# Audio_Jack_Interface.net
KiCad netlist of a schematic drawn in EAGLE
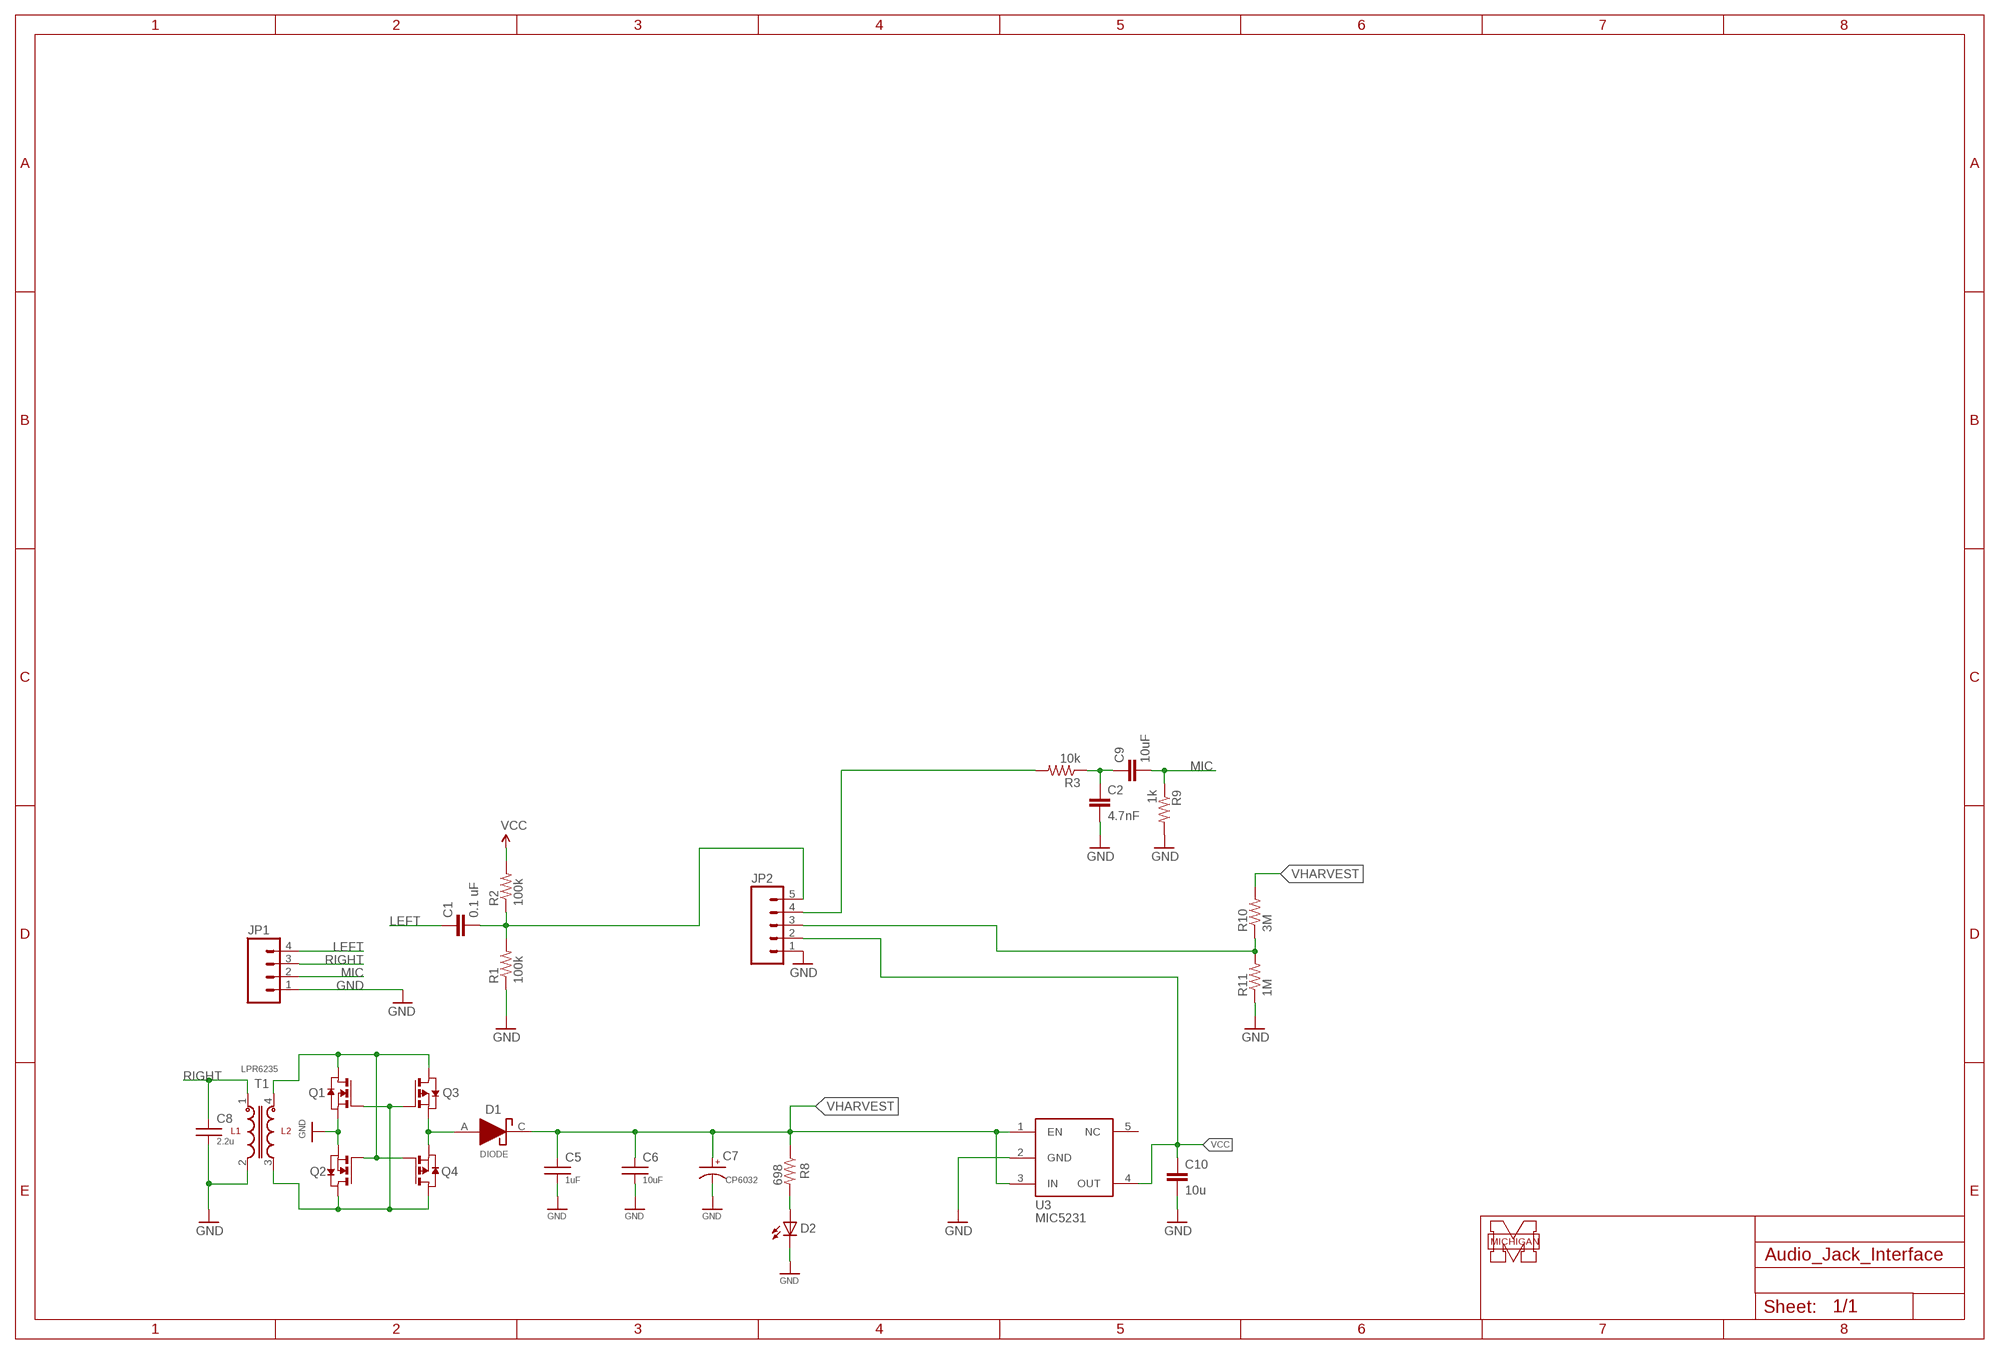
[diagram p0: schematic, sheet 1]

(export (version "E")
  (design (tool "Eeschema 10.0.6"))
  (components
    (comp (ref "C1")
      (value "0.1 uF")
      (footprint "eagle-import:0603-CAP")
      (libsource (lib "eagle-import") (part "CAP0603-CAP"))
    )
    (comp (ref "C2")
      (value "4.7nF")
      (footprint "eagle-import:0603-CAP")
      (libsource (lib "eagle-import") (part "CAP0603-CAP"))
    )
    (comp (ref "C5")
      (value "1uF")
      (footprint "eagle-import:C0603")
      (libsource (lib "eagle-import") (part "C0603"))
    )
    (comp (ref "C6")
      (value "10uF")
      (footprint "eagle-import:C0603")
      (libsource (lib "eagle-import") (part "C0603"))
    )
    (comp (ref "C7")
      (value "CP6032")
      (footprint "eagle-import:CT6032")
      (libsource (lib "eagle-import") (part "CP6032"))
    )
    (comp (ref "C8")
      (value "2.2u")
      (footprint "eagle-import:C0603")
      (libsource (lib "eagle-import") (part "C0603"))
    )
    (comp (ref "C9")
      (value "10uF")
      (footprint "eagle-import:0603-CAP")
      (libsource (lib "eagle-import") (part "CAP0603-CAP"))
    )
    (comp (ref "C10")
      (value "10u")
      (footprint "eagle-import:C0603")
      (libsource (lib "eagle-import") (part "C-EUC0603"))
    )
    (comp (ref "D1")
      (value "DIODE")
      (footprint "eagle-import:MINIMELF")
      (libsource (lib "eagle-import") (part "DIODE"))
    )
    (comp (ref "D2")
      (value "LED0603")
      (footprint "eagle-import:LED-0603")
      (libsource (lib "eagle-import") (part "LED0603"))
    )
    (comp (ref "JP1")
      (value "M041.27MM")
      (footprint "eagle-import:1X04-1.27MM")
      (libsource (lib "eagle-import") (part "M041.27MM"))
    )
    (comp (ref "JP2")
      (value "M05PTH")
      (footprint "eagle-import:1X05")
      (libsource (lib "eagle-import") (part "M05PTH"))
    )
    (comp (ref "Q1")
      (value "NMOSSOT23")
      (footprint "eagle-import:SOT-23")
      (libsource (lib "eagle-import") (part "NMOSSOT23"))
    )
    (comp (ref "Q2")
      (value "NMOSSOT23")
      (footprint "eagle-import:SOT-23")
      (libsource (lib "eagle-import") (part "NMOSSOT23"))
    )
    (comp (ref "Q3")
      (value "PMOSSOT23")
      (footprint "eagle-import:SOT-23")
      (libsource (lib "eagle-import") (part "PMOSSOT23"))
    )
    (comp (ref "Q4")
      (value "PMOSSOT23")
      (footprint "eagle-import:SOT-23")
      (libsource (lib "eagle-import") (part "PMOSSOT23"))
    )
    (comp (ref "R1")
      (value "100k")
      (footprint "eagle-import:0603-RES")
      (libsource (lib "eagle-import") (part "RESISTOR0603-RES"))
    )
    (comp (ref "R2")
      (value "100k")
      (footprint "eagle-import:0603-RES")
      (libsource (lib "eagle-import") (part "RESISTOR0603-RES"))
    )
    (comp (ref "R3")
      (value "10k")
      (footprint "eagle-import:0603-RES")
      (libsource (lib "eagle-import") (part "RESISTOR0603-RES"))
    )
    (comp (ref "R8")
      (value "698")
      (footprint "eagle-import:R0603")
      (libsource (lib "eagle-import") (part "R-US_R0603"))
    )
    (comp (ref "R9")
      (value "1k")
      (footprint "eagle-import:0603-RES")
      (libsource (lib "eagle-import") (part "RESISTOR0603-RES"))
    )
    (comp (ref "R10")
      (value "3M")
      (footprint "eagle-import:0603-RES")
      (libsource (lib "eagle-import") (part "RESISTOR0603-RES"))
    )
    (comp (ref "R11")
      (value "1M")
      (footprint "eagle-import:0603-RES")
      (libsource (lib "eagle-import") (part "RESISTOR0603-RES"))
    )
    (comp (ref "T1")
      (value "LPR6235")
      (footprint "eagle-import:LPR6235")
      (libsource (lib "eagle-import") (part "LPR6235"))
    )
    (comp (ref "U3")
      (value "MIC5231")
      (footprint "eagle-import:SOT23-5")
      (libsource (lib "eagle-import") (part "MIC5231"))
    )
  )
  (nets
    (net (code "1") (name "/LEFT") (class "Default")
      (node (ref "C1") (pin "1") (pinfunction "1_1") (pintype "passive"))
      (node (ref "JP1") (pin "4") (pinfunction "4_4") (pintype "passive"))
    )
    (net (code "2") (name "/MIC") (class "Default")
      (node (ref "C9") (pin "2") (pinfunction "2_2") (pintype "passive"))
      (node (ref "JP1") (pin "2") (pinfunction "2_2") (pintype "passive"))
      (node (ref "R9") (pin "1") (pinfunction "1_1") (pintype "passive"))
    )
    (net (code "3") (name "/RIGHT") (class "Default")
      (node (ref "C8") (pin "1") (pinfunction "1_1") (pintype "bidirectional"))
      (node (ref "JP1") (pin "3") (pinfunction "3_3") (pintype "passive"))
      (node (ref "T1") (pin "1") (pinfunction "1_1") (pintype "bidirectional"))
    )
    (net (code "4") (name "GND") (class "Default")
      (node (ref "C10") (pin "2") (pinfunction "2_2") (pintype "passive"))
      (node (ref "C2") (pin "2") (pinfunction "2_2") (pintype "passive"))
      (node (ref "C5") (pin "2") (pinfunction "2_2") (pintype "bidirectional"))
      (node (ref "C6") (pin "2") (pinfunction "2_2") (pintype "bidirectional"))
      (node (ref "C7") (pin "-") (pinfunction "-_-") (pintype "bidirectional"))
      (node (ref "C8") (pin "2") (pinfunction "2_2") (pintype "bidirectional"))
      (node (ref "D2") (pin "C") (pinfunction "C_C") (pintype "passive"))
      (node (ref "JP1") (pin "1") (pinfunction "1_1") (pintype "passive"))
      (node (ref "JP2") (pin "1") (pinfunction "1_1") (pintype "passive"))
      (node (ref "Q1") (pin "2") (pinfunction "S_2") (pintype "passive"))
      (node (ref "Q2") (pin "2") (pinfunction "S_2") (pintype "passive"))
      (node (ref "R1") (pin "1") (pinfunction "1_1") (pintype "passive"))
      (node (ref "R11") (pin "1") (pinfunction "1_1") (pintype "passive"))
      (node (ref "R9") (pin "2") (pinfunction "2_2") (pintype "passive"))
      (node (ref "T1") (pin "2") (pinfunction "2_2") (pintype "bidirectional"))
      (node (ref "U3") (pin "2") (pinfunction "GND_2") (pintype "bidirectional"))
    )
    (net (code "5") (name "Net-(C1-Pad2)") (class "Default")
      (node (ref "C1") (pin "2") (pinfunction "2_2") (pintype "passive"))
      (node (ref "JP2") (pin "5") (pinfunction "5_5") (pintype "passive"))
      (node (ref "R1") (pin "2") (pinfunction "2_2") (pintype "passive"))
      (node (ref "R2") (pin "1") (pinfunction "1_1") (pintype "passive"))
    )
    (net (code "6") (name "Net-(C2-Pad1)") (class "Default")
      (node (ref "C2") (pin "1") (pinfunction "1_1") (pintype "passive"))
      (node (ref "C9") (pin "1") (pinfunction "1_1") (pintype "passive"))
      (node (ref "R3") (pin "1") (pinfunction "1_1") (pintype "passive"))
    )
    (net (code "7") (name "Net-(D2-PadA)") (class "Default")
      (node (ref "D2") (pin "A") (pinfunction "A_A") (pintype "passive"))
      (node (ref "R8") (pin "2") (pinfunction "2_2") (pintype "passive"))
    )
    (net (code "8") (name "Net-(JP2-Pad3)") (class "Default")
      (node (ref "JP2") (pin "3") (pinfunction "3_3") (pintype "passive"))
      (node (ref "R10") (pin "1") (pinfunction "1_1") (pintype "passive"))
      (node (ref "R11") (pin "2") (pinfunction "2_2") (pintype "passive"))
    )
    (net (code "9") (name "Net-(JP2-Pad4)") (class "Default")
      (node (ref "JP2") (pin "4") (pinfunction "4_4") (pintype "passive"))
      (node (ref "R3") (pin "2") (pinfunction "2_2") (pintype "passive"))
    )
    (net (code "10") (name "Net-(Q1-D)") (class "Default")
      (node (ref "Q1") (pin "1") (pinfunction "D_1") (pintype "passive"))
      (node (ref "Q2") (pin "3") (pinfunction "G_3") (pintype "passive"))
      (node (ref "Q3") (pin "1") (pinfunction "D_1") (pintype "passive"))
      (node (ref "Q4") (pin "3") (pinfunction "G_3") (pintype "passive"))
      (node (ref "T1") (pin "4") (pinfunction "4_4") (pintype "bidirectional"))
    )
    (net (code "11") (name "Net-(Q1-G)") (class "Default")
      (node (ref "Q1") (pin "3") (pinfunction "G_3") (pintype "passive"))
      (node (ref "Q2") (pin "1") (pinfunction "D_1") (pintype "passive"))
      (node (ref "Q3") (pin "3") (pinfunction "G_3") (pintype "passive"))
      (node (ref "Q4") (pin "1") (pinfunction "D_1") (pintype "passive"))
      (node (ref "T1") (pin "3") (pinfunction "3_3") (pintype "bidirectional"))
    )
    (net (code "12") (name "Net-(Q3-S)") (class "Default")
      (node (ref "D1") (pin "A") (pinfunction "A_A") (pintype "bidirectional"))
      (node (ref "Q3") (pin "2") (pinfunction "S_2") (pintype "passive"))
      (node (ref "Q4") (pin "2") (pinfunction "S_2") (pintype "passive"))
    )
    (net (code "13") (name "VCC") (class "Default")
      (node (ref "C10") (pin "1") (pinfunction "1_1") (pintype "passive"))
      (node (ref "JP2") (pin "2") (pinfunction "2_2") (pintype "passive"))
      (node (ref "R2") (pin "2") (pinfunction "2_2") (pintype "passive"))
      (node (ref "U3") (pin "4") (pinfunction "OUT_4") (pintype "bidirectional"))
    )
    (net (code "14") (name "VHARVEST") (class "Default")
      (node (ref "C5") (pin "1") (pinfunction "1_1") (pintype "bidirectional"))
      (node (ref "C6") (pin "1") (pinfunction "1_1") (pintype "bidirectional"))
      (node (ref "C7") (pin "+") (pinfunction "+_+") (pintype "bidirectional"))
      (node (ref "D1") (pin "C") (pinfunction "C_C") (pintype "bidirectional"))
      (node (ref "R10") (pin "2") (pinfunction "2_2") (pintype "passive"))
      (node (ref "R8") (pin "1") (pinfunction "1_1") (pintype "passive"))
      (node (ref "U3") (pin "1") (pinfunction "EN_1") (pintype "bidirectional"))
      (node (ref "U3") (pin "3") (pinfunction "IN_3") (pintype "bidirectional"))
    )
    (net (code "15") (name "unconnected-(U3-NC-Pad5)") (class "Default")
      (node (ref "U3") (pin "5") (pinfunction "NC_5") (pintype "bidirectional"))
    )
  )
)
